# IR_Receivers.net
KiCad netlist of a schematic drawn in Altium Designer
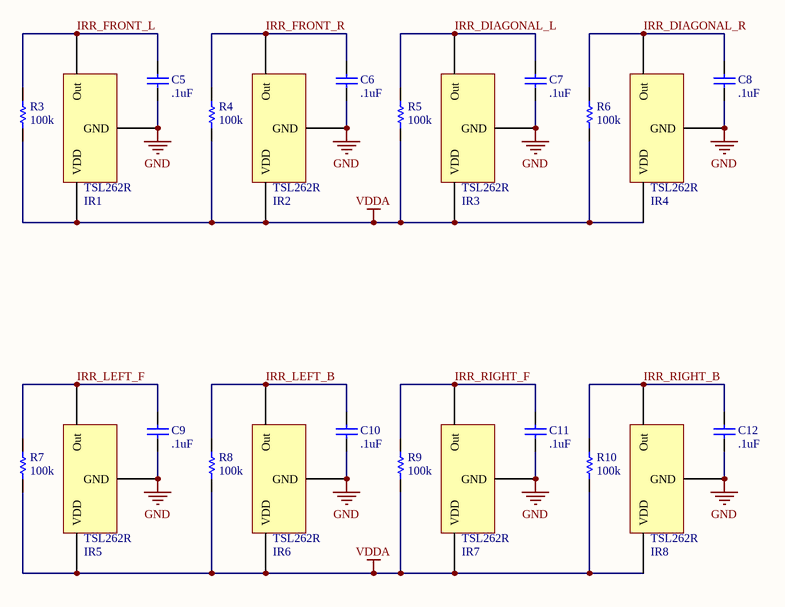
[diagram p0: IR_Receivers.SchDoc]

(export (version "E")
  (design (tool "Eeschema 10.0.6"))
  (components
    (comp (ref "C5")
      (value ".1uF")
      (footprint "1608[0603]")
      (description "Capacitor (Semiconductor SIM Model)")
      (fields (field (name "Comment") "Cap Semi") (field (name "PUBLISHER") "Altium Limited"))
      (libsource (lib "Miscellaneous Devices") (part "Cap Semi"))
    )
    (comp (ref "C6")
      (value ".1uF")
      (footprint "1608[0603]")
      (description "Capacitor (Semiconductor SIM Model)")
      (fields (field (name "Comment") "Cap Semi") (field (name "PUBLISHER") "Altium Limited"))
      (libsource (lib "Miscellaneous Devices") (part "Cap Semi"))
    )
    (comp (ref "C7")
      (value ".1uF")
      (footprint "1608[0603]")
      (description "Capacitor (Semiconductor SIM Model)")
      (fields (field (name "Comment") "Cap Semi") (field (name "PUBLISHER") "Altium Limited"))
      (libsource (lib "Miscellaneous Devices") (part "Cap Semi"))
    )
    (comp (ref "C8")
      (value ".1uF")
      (footprint "1608[0603]")
      (description "Capacitor (Semiconductor SIM Model)")
      (fields (field (name "Comment") "Cap Semi") (field (name "PUBLISHER") "Altium Limited"))
      (libsource (lib "Miscellaneous Devices") (part "Cap Semi"))
    )
    (comp (ref "C9")
      (value ".1uF")
      (footprint "1608[0603]")
      (description "Capacitor (Semiconductor SIM Model)")
      (fields (field (name "Comment") "Cap Semi") (field (name "PUBLISHER") "Altium Limited"))
      (libsource (lib "Miscellaneous Devices") (part "Cap Semi"))
    )
    (comp (ref "C10")
      (value ".1uF")
      (footprint "1608[0603]")
      (description "Capacitor (Semiconductor SIM Model)")
      (fields (field (name "Comment") "Cap Semi") (field (name "PUBLISHER") "Altium Limited"))
      (libsource (lib "Miscellaneous Devices") (part "Cap Semi"))
    )
    (comp (ref "C11")
      (value ".1uF")
      (footprint "1608[0603]")
      (description "Capacitor (Semiconductor SIM Model)")
      (fields (field (name "Comment") "Cap Semi") (field (name "PUBLISHER") "Altium Limited"))
      (libsource (lib "Miscellaneous Devices") (part "Cap Semi"))
    )
    (comp (ref "C12")
      (value ".1uF")
      (footprint "1608[0603]")
      (description "Capacitor (Semiconductor SIM Model)")
      (fields (field (name "Comment") "Cap Semi") (field (name "PUBLISHER") "Altium Limited"))
      (libsource (lib "Miscellaneous Devices") (part "Cap Semi"))
    )
    (comp (ref "IR1") (value "TSL262R") (footprint "TSL262R") (libsource (lib "Devices") (part "TSL262R")))
    (comp (ref "IR2") (value "TSL262R") (footprint "TSL262R") (libsource (lib "Devices") (part "TSL262R")))
    (comp (ref "IR3") (value "TSL262R") (footprint "TSL262R") (libsource (lib "Devices") (part "TSL262R")))
    (comp (ref "IR4") (value "TSL262R") (footprint "TSL262R") (libsource (lib "Devices") (part "TSL262R")))
    (comp (ref "IR5") (value "TSL262R") (footprint "TSL262R") (libsource (lib "Devices") (part "TSL262R")))
    (comp (ref "IR6") (value "TSL262R") (footprint "TSL262R") (libsource (lib "Devices") (part "TSL262R")))
    (comp (ref "IR7") (value "TSL262R") (footprint "TSL262R") (libsource (lib "Devices") (part "TSL262R")))
    (comp (ref "IR8") (value "TSL262R") (footprint "TSL262R") (libsource (lib "Devices") (part "TSL262R")))
    (comp (ref "R3")
      (value "100k")
      (footprint "0603")
      (description "Resistor")
      (fields (field (name "PUBLISHER") "Altium Limited"))
      (libsource (lib "passives") (part "Resistor"))
    )
    (comp (ref "R4")
      (value "100k")
      (footprint "0603")
      (description "Resistor")
      (fields (field (name "PUBLISHER") "Altium Limited"))
      (libsource (lib "passives") (part "Resistor"))
    )
    (comp (ref "R5")
      (value "100k")
      (footprint "0603")
      (description "Resistor")
      (fields (field (name "PUBLISHER") "Altium Limited"))
      (libsource (lib "passives") (part "Resistor"))
    )
    (comp (ref "R6")
      (value "100k")
      (footprint "0603")
      (description "Resistor")
      (fields (field (name "PUBLISHER") "Altium Limited"))
      (libsource (lib "passives") (part "Resistor"))
    )
    (comp (ref "R7")
      (value "100k")
      (footprint "0603")
      (description "Resistor")
      (fields (field (name "PUBLISHER") "Altium Limited"))
      (libsource (lib "passives") (part "Resistor"))
    )
    (comp (ref "R8")
      (value "100k")
      (footprint "0603")
      (description "Resistor")
      (fields (field (name "PUBLISHER") "Altium Limited"))
      (libsource (lib "passives") (part "Resistor"))
    )
    (comp (ref "R9")
      (value "100k")
      (footprint "0603")
      (description "Resistor")
      (fields (field (name "PUBLISHER") "Altium Limited"))
      (libsource (lib "passives") (part "Resistor"))
    )
    (comp (ref "R10")
      (value "100k")
      (footprint "0603")
      (description "Resistor")
      (fields (field (name "PUBLISHER") "Altium Limited"))
      (libsource (lib "passives") (part "Resistor"))
    )
  )
  (nets
    (net (code "1") (name "/IRR_DIAGONAL_L") (class "Default")
      (node (ref "C7") (pin "2") (pinfunction "2_2") (pintype "passive"))
      (node (ref "IR3") (pin "2") (pinfunction "Out_2") (pintype "passive"))
      (node (ref "R5") (pin "2") (pinfunction "2_2") (pintype "passive"))
    )
    (net (code "2") (name "/IRR_DIAGONAL_R") (class "Default")
      (node (ref "C8") (pin "2") (pinfunction "2_2") (pintype "passive"))
      (node (ref "IR4") (pin "2") (pinfunction "Out_2") (pintype "passive"))
      (node (ref "R6") (pin "2") (pinfunction "2_2") (pintype "passive"))
    )
    (net (code "3") (name "/IRR_FRONT_L") (class "Default")
      (node (ref "C5") (pin "2") (pinfunction "2_2") (pintype "passive"))
      (node (ref "IR1") (pin "2") (pinfunction "Out_2") (pintype "passive"))
      (node (ref "R3") (pin "2") (pinfunction "2_2") (pintype "passive"))
    )
    (net (code "4") (name "/IRR_FRONT_R") (class "Default")
      (node (ref "C6") (pin "2") (pinfunction "2_2") (pintype "passive"))
      (node (ref "IR2") (pin "2") (pinfunction "Out_2") (pintype "passive"))
      (node (ref "R4") (pin "2") (pinfunction "2_2") (pintype "passive"))
    )
    (net (code "5") (name "/IRR_LEFT_B") (class "Default")
      (node (ref "C10") (pin "2") (pinfunction "2_2") (pintype "passive"))
      (node (ref "IR6") (pin "2") (pinfunction "Out_2") (pintype "passive"))
      (node (ref "R8") (pin "2") (pinfunction "2_2") (pintype "passive"))
    )
    (net (code "6") (name "/IRR_LEFT_F") (class "Default")
      (node (ref "C9") (pin "2") (pinfunction "2_2") (pintype "passive"))
      (node (ref "IR5") (pin "2") (pinfunction "Out_2") (pintype "passive"))
      (node (ref "R7") (pin "2") (pinfunction "2_2") (pintype "passive"))
    )
    (net (code "7") (name "/IRR_RIGHT_B") (class "Default")
      (node (ref "C12") (pin "2") (pinfunction "2_2") (pintype "passive"))
      (node (ref "IR8") (pin "2") (pinfunction "Out_2") (pintype "passive"))
      (node (ref "R10") (pin "2") (pinfunction "2_2") (pintype "passive"))
    )
    (net (code "8") (name "/IRR_RIGHT_F") (class "Default")
      (node (ref "C11") (pin "2") (pinfunction "2_2") (pintype "passive"))
      (node (ref "IR7") (pin "2") (pinfunction "Out_2") (pintype "passive"))
      (node (ref "R9") (pin "2") (pinfunction "2_2") (pintype "passive"))
    )
    (net (code "9") (name "GND") (class "Default")
      (node (ref "C10") (pin "1") (pinfunction "1_1") (pintype "passive"))
      (node (ref "C11") (pin "1") (pinfunction "1_1") (pintype "passive"))
      (node (ref "C12") (pin "1") (pinfunction "1_1") (pintype "passive"))
      (node (ref "C5") (pin "1") (pinfunction "1_1") (pintype "passive"))
      (node (ref "C6") (pin "1") (pinfunction "1_1") (pintype "passive"))
      (node (ref "C7") (pin "1") (pinfunction "1_1") (pintype "passive"))
      (node (ref "C8") (pin "1") (pinfunction "1_1") (pintype "passive"))
      (node (ref "C9") (pin "1") (pinfunction "1_1") (pintype "passive"))
      (node (ref "IR1") (pin "0") (pinfunction "GND_0") (pintype "passive"))
      (node (ref "IR2") (pin "0") (pinfunction "GND_0") (pintype "passive"))
      (node (ref "IR3") (pin "0") (pinfunction "GND_0") (pintype "passive"))
      (node (ref "IR4") (pin "0") (pinfunction "GND_0") (pintype "passive"))
      (node (ref "IR5") (pin "0") (pinfunction "GND_0") (pintype "passive"))
      (node (ref "IR6") (pin "0") (pinfunction "GND_0") (pintype "passive"))
      (node (ref "IR7") (pin "0") (pinfunction "GND_0") (pintype "passive"))
      (node (ref "IR8") (pin "0") (pinfunction "GND_0") (pintype "passive"))
    )
    (net (code "10") (name "VDDA") (class "Default")
      (node (ref "IR1") (pin "1") (pinfunction "VDD_1") (pintype "passive"))
      (node (ref "IR2") (pin "1") (pinfunction "VDD_1") (pintype "passive"))
      (node (ref "IR3") (pin "1") (pinfunction "VDD_1") (pintype "passive"))
      (node (ref "IR4") (pin "1") (pinfunction "VDD_1") (pintype "passive"))
      (node (ref "IR5") (pin "1") (pinfunction "VDD_1") (pintype "passive"))
      (node (ref "IR6") (pin "1") (pinfunction "VDD_1") (pintype "passive"))
      (node (ref "IR7") (pin "1") (pinfunction "VDD_1") (pintype "passive"))
      (node (ref "IR8") (pin "1") (pinfunction "VDD_1") (pintype "passive"))
      (node (ref "R10") (pin "1") (pinfunction "1_1") (pintype "passive"))
      (node (ref "R3") (pin "1") (pinfunction "1_1") (pintype "passive"))
      (node (ref "R4") (pin "1") (pinfunction "1_1") (pintype "passive"))
      (node (ref "R5") (pin "1") (pinfunction "1_1") (pintype "passive"))
      (node (ref "R6") (pin "1") (pinfunction "1_1") (pintype "passive"))
      (node (ref "R7") (pin "1") (pinfunction "1_1") (pintype "passive"))
      (node (ref "R8") (pin "1") (pinfunction "1_1") (pintype "passive"))
      (node (ref "R9") (pin "1") (pinfunction "1_1") (pintype "passive"))
    )
  )
)
